# SD3078.net
KiCad netlist of a schematic drawn in Altium Designer
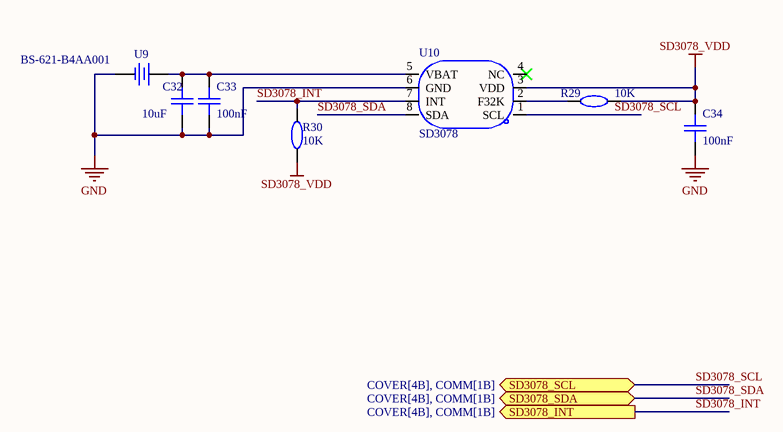
[diagram p0: SD3078.SchDoc]

(export (version "E")
  (design (tool "Eeschema 10.0.6"))
  (components
    (comp (ref "C32")
      (value "10uF")
      (footprint "C0603")
      (fields (field (name "NAME") "10uF"))
      (libsource (lib "my_library") (part "CAP_0603"))
    )
    (comp (ref "C33")
      (value "100nF")
      (footprint "C0402")
      (fields (field (name "NAME") "100nF"))
      (libsource (lib "my_library") (part "CAP_0402"))
    )
    (comp (ref "C34")
      (value "100nF")
      (footprint "C0402")
      (fields (field (name "NAME") "100nF"))
      (libsource (lib "my_library") (part "CAP_0402"))
    )
    (comp (ref "R29")
      (value "10K")
      (footprint "R0402")
      (fields (field (name "NAME") "10K"))
      (libsource (lib "my_library") (part "Res_0402"))
    )
    (comp (ref "R30")
      (value "10K")
      (footprint "R0402")
      (fields (field (name "NAME") "10K"))
      (libsource (lib "my_library") (part "Res_0402"))
    )
    (comp (ref "U9")
      (value "BS-621-B4AA001")
      (footprint "BAT-SMD_BS-621-B4AA001")
      (fields (field (name "MANUFACTURER") "MYOUNG(美阳)") (field (name "NAME") "BS-621-B4AA001"))
      (libsource (lib "my_library") (part "BS-621-B4AA001"))
    )
    (comp (ref "U10")
      (value "SD3078")
      (footprint "SOP-8_L5.3-W5.2-P1.27-LS7.9-BL")
      (fields (field (name "MANUFACTURER") "WAVE(兴威帆电子)") (field (name "NAME") "SD3078"))
      (libsource (lib "my_library") (part "SD3078"))
    )
  )
  (nets
    (net (code "1") (name "/SD3078_INT") (class "Default")
      (node (ref "R30") (pin "2") (pinfunction "2_2") (pintype "passive"))
      (node (ref "U10") (pin "7") (pinfunction "INT_7") (pintype "passive"))
    )
    (net (code "2") (name "/SD3078_SCL") (class "Default")
      (node (ref "U10") (pin "1") (pinfunction "SCL_1") (pintype "passive"))
    )
    (net (code "3") (name "/SD3078_SDA") (class "Default")
      (node (ref "U10") (pin "8") (pinfunction "SDA_8") (pintype "passive"))
    )
    (net (code "4") (name "GND") (class "Default")
      (node (ref "C32") (pin "1") (pinfunction "1_1") (pintype "passive"))
      (node (ref "C33") (pin "1") (pinfunction "1_1") (pintype "passive"))
      (node (ref "C34") (pin "1") (pinfunction "1_1") (pintype "passive"))
      (node (ref "U10") (pin "6") (pinfunction "GND_6") (pintype "passive"))
      (node (ref "U9") (pin "1") (pinfunction "1_1") (pintype "passive"))
    )
    (net (code "5") (name "Net-(U10-F32K)") (class "Default")
      (node (ref "R29") (pin "1") (pinfunction "1_1") (pintype "passive"))
      (node (ref "U10") (pin "2") (pinfunction "F32K_2") (pintype "passive"))
    )
    (net (code "6") (name "Net-(U10-VBAT)") (class "Default")
      (node (ref "C32") (pin "2") (pinfunction "2_2") (pintype "passive"))
      (node (ref "C33") (pin "2") (pinfunction "2_2") (pintype "passive"))
      (node (ref "U10") (pin "5") (pinfunction "VBAT_5") (pintype "passive"))
      (node (ref "U9") (pin "2") (pinfunction "2_2") (pintype "passive"))
    )
    (net (code "7") (name "SD3078_VDD") (class "Default")
      (node (ref "C34") (pin "2") (pinfunction "2_2") (pintype "passive"))
      (node (ref "R29") (pin "2") (pinfunction "2_2") (pintype "passive"))
      (node (ref "R30") (pin "1") (pinfunction "1_1") (pintype "passive"))
      (node (ref "U10") (pin "3") (pinfunction "VDD_3") (pintype "passive"))
    )
    (net (code "8") (name "unconnected-(U10-NC-Pad4)") (class "Default")
      (node (ref "U10") (pin "4") (pinfunction "NC_4") (pintype "passive+no_connect"))
    )
  )
)
